# V1_1.net
KiCad netlist of a schematic drawn in EAGLE
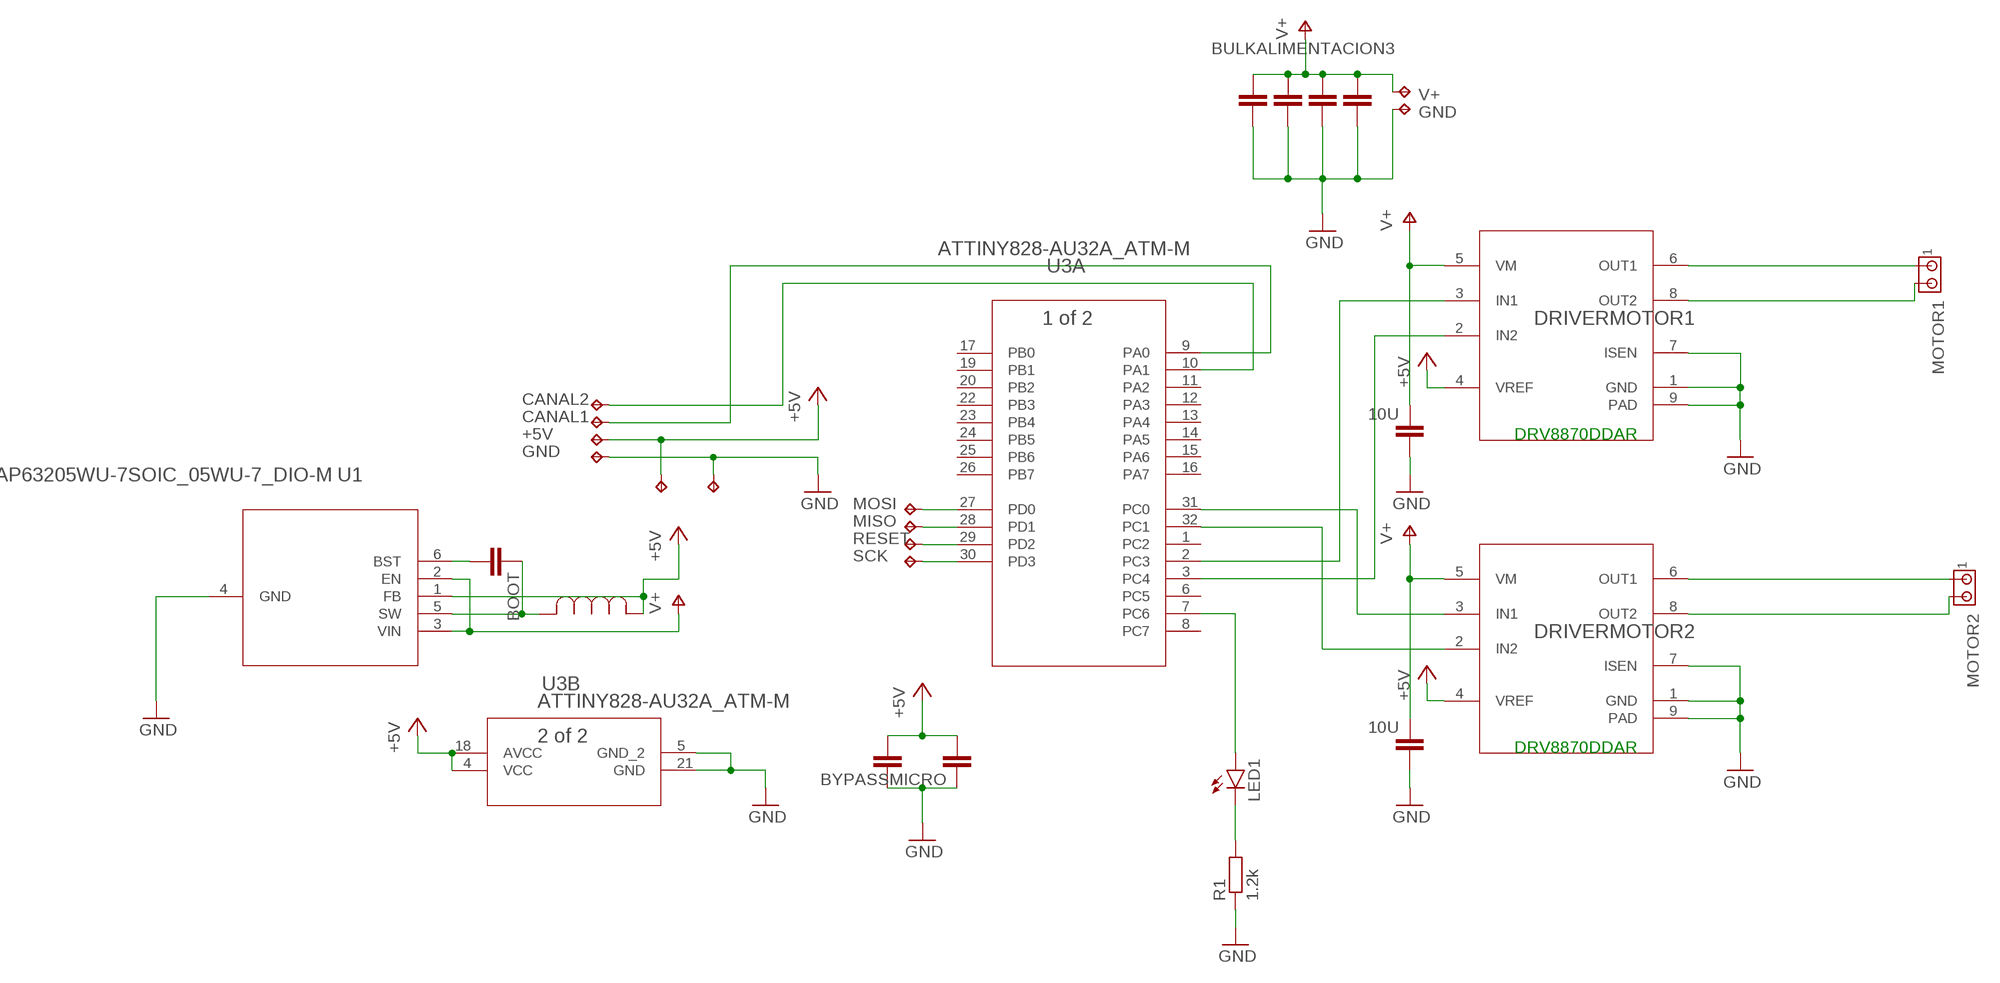
[diagram p0: schematic, sheet 1]

(export (version "E")
  (design (tool "Eeschema 10.0.6"))
  (components
    (comp (ref "BOOT")
      (value "C-EUC0402")
      (footprint "eagle-import:C0402")
      (libsource (lib "eagle-import") (part "C-EUC0402"))
    )
    (comp (ref "BULKALIMENTACION")
      (value "C-EUC1206")
      (footprint "eagle-import:C1206")
      (libsource (lib "eagle-import") (part "C-EUC1206"))
    )
    (comp (ref "BULKALIMENTACION1")
      (value "C-EUC1206")
      (footprint "eagle-import:C1206")
      (libsource (lib "eagle-import") (part "C-EUC1206"))
    )
    (comp (ref "BULKALIMENTACION2")
      (value "C-EUC1206")
      (footprint "eagle-import:C1206")
      (libsource (lib "eagle-import") (part "C-EUC1206"))
    )
    (comp (ref "BULKALIMENTACION3")
      (value "C-EUC1206")
      (footprint "eagle-import:C1206")
      (libsource (lib "eagle-import") (part "C-EUC1206"))
    )
    (comp (ref "BYPASS1")
      (value "10U")
      (footprint "eagle-import:C0603")
      (libsource (lib "eagle-import") (part "C-EUC0603"))
    )
    (comp (ref "BYPASSMICRO")
      (value "C-EUC0603")
      (footprint "eagle-import:C0603")
      (libsource (lib "eagle-import") (part "C-EUC0603"))
    )
    (comp (ref "BYPASSMICRO2")
      (value "C-EUC0603")
      (footprint "eagle-import:C0603")
      (libsource (lib "eagle-import") (part "C-EUC0603"))
    )
    (comp (ref "BYPASSMOTOR2")
      (value "10U")
      (footprint "eagle-import:C0603")
      (libsource (lib "eagle-import") (part "C-EUC0603"))
    )
    (comp (ref "DRIVERMOTOR1")
      (value "DRV8870")
      (footprint "eagle-import:DDA0008H_N")
      (libsource (lib "eagle-import") (part "DRV8870"))
    )
    (comp (ref "DRIVERMOTOR2")
      (value "DRV8870")
      (footprint "eagle-import:DDA0008H_N")
      (libsource (lib "eagle-import") (part "DRV8870"))
    )
    (comp (ref "GND")
      (value "TPTP20SQ")
      (footprint "eagle-import:TP20SQ")
      (libsource (lib "eagle-import") (part "TPTP20SQ"))
    )
    (comp (ref "LED1")
      (value "LEDCHIPLED_0603")
      (footprint "eagle-import:CHIPLED_0603")
      (libsource (lib "eagle-import") (part "LEDCHIPLED_0603"))
    )
    (comp (ref "MISO")
      (value "TPTP12R")
      (footprint "eagle-import:TP12R")
      (libsource (lib "eagle-import") (part "TPTP12R"))
    )
    (comp (ref "MOTOR1")
      (value "MTA02-100")
      (footprint "eagle-import:10X02MTA")
      (libsource (lib "eagle-import") (part "MTA02-100"))
    )
    (comp (ref "MOTOR2")
      (value "MTA02-100")
      (footprint "eagle-import:10X02MTA")
      (libsource (lib "eagle-import") (part "MTA02-100"))
    )
    (comp (ref "R1")
      (value "1.2k")
      (footprint "eagle-import:R0603")
      (libsource (lib "eagle-import") (part "R-EU_R0603"))
    )
    (comp (ref "TP1")
      (value "TPTP13SQ")
      (footprint "eagle-import:TP13SQ")
      (libsource (lib "eagle-import") (part "TPTP13SQ"))
    )
    (comp (ref "TP2")
      (value "TPTP13SQ")
      (footprint "eagle-import:TP13SQ")
      (libsource (lib "eagle-import") (part "TPTP13SQ"))
    )
    (comp (ref "TP3")
      (value "TPTP13SQ")
      (footprint "eagle-import:TP13SQ")
      (libsource (lib "eagle-import") (part "TPTP13SQ"))
    )
    (comp (ref "TP4")
      (value "TPTP13SQ")
      (footprint "eagle-import:TP13SQ")
      (libsource (lib "eagle-import") (part "TPTP13SQ"))
    )
    (comp (ref "TP5")
      (value "TPTP13SQ")
      (footprint "eagle-import:TP13SQ")
      (libsource (lib "eagle-import") (part "TPTP13SQ"))
    )
    (comp (ref "TP6")
      (value "TPTP12R")
      (footprint "eagle-import:TP12R")
      (libsource (lib "eagle-import") (part "TPTP12R"))
    )
    (comp (ref "TP7")
      (value "TPTP12R")
      (footprint "eagle-import:TP12R")
      (libsource (lib "eagle-import") (part "TPTP12R"))
    )
    (comp (ref "TP8")
      (value "TPTP12R")
      (footprint "eagle-import:TP12R")
      (libsource (lib "eagle-import") (part "TPTP12R"))
    )
    (comp (ref "TP9")
      (value "TPTP13SQ")
      (footprint "eagle-import:TP13SQ")
      (libsource (lib "eagle-import") (part "TPTP13SQ"))
    )
    (comp (ref "U$2")
      (value "INDUCTOR4.7")
      (footprint "eagle-import:IND_NRS5030T100MMGJ_TAY")
      (libsource (lib "eagle-import") (part "INDUCTOR4.7"))
    )
    (comp (ref "U1")
      (value "AP63205WU-7SOIC_05WU-7_DIO-M")
      (footprint "eagle-import:SOIC_05WU-7_DIO-M")
      (fields
        (field (name "MANUFACTURER_PART_NUMBER") "AP63205WU-7")
        (field (name "COPYRIGHT") "Copyright (C) 2018 Accelerated Designs. All rights reserved")
      )
      (libsource (lib "eagle-import") (part "AP63205WU-7SOIC_05WU-7_DIO-M"))
    )
    (comp (ref "U3")
      (value "ATTINY828-AU32A_ATM-M")
      (footprint "eagle-import:32A_ATM-M")
      (fields (field (name "MANUFACTURER_PART_NUMBER") "ATTINY828-AU"))
      (libsource (lib "eagle-import") (part "ATTINY828-AU32A_ATM-M"))
    )
    (comp (ref "V+")
      (value "TPTP20SQ")
      (footprint "eagle-import:TP20SQ")
      (libsource (lib "eagle-import") (part "TPTP20SQ"))
    )
  )
  (nets
    (net (code "1") (name "+5V") (class "Default")
      (node (ref "BYPASSMICRO") (pin "2") (pinfunction "2_2") (pintype "passive"))
      (node (ref "BYPASSMICRO2") (pin "2") (pinfunction "2_2") (pintype "passive"))
      (node (ref "DRIVERMOTOR1") (pin "4") (pinfunction "VREF_4") (pintype "input"))
      (node (ref "DRIVERMOTOR2") (pin "4") (pinfunction "VREF_4") (pintype "input"))
      (node (ref "TP3") (pin "TP") (pinfunction "TP_TP") (pintype "input"))
      (node (ref "TP9") (pin "TP") (pinfunction "TP_TP") (pintype "input"))
      (node (ref "U$2") (pin "1") (pinfunction "1_1") (pintype "passive"))
      (node (ref "U1") (pin "1") (pinfunction "FB_1") (pintype "passive"))
      (node (ref "U3") (pin "18") (pinfunction "AVCC_18") (pintype "power_in"))
      (node (ref "U3") (pin "4") (pinfunction "VCC_4") (pintype "power_in"))
    )
    (net (code "2") (name "/CANAL1") (class "Default")
      (node (ref "TP1") (pin "TP") (pinfunction "TP_TP") (pintype "input"))
      (node (ref "U3") (pin "9") (pinfunction "PA0_9") (pintype "bidirectional"))
    )
    (net (code "3") (name "/CANAL2") (class "Default")
      (node (ref "TP2") (pin "TP") (pinfunction "TP_TP") (pintype "input"))
      (node (ref "U3") (pin "10") (pinfunction "PA1_10") (pintype "bidirectional"))
    )
    (net (code "4") (name "/MISO") (class "Default")
      (node (ref "TP6") (pin "TP") (pinfunction "TP_TP") (pintype "input"))
      (node (ref "U3") (pin "28") (pinfunction "PD1_28") (pintype "bidirectional"))
    )
    (net (code "5") (name "/MOSI") (class "Default")
      (node (ref "MISO") (pin "TP") (pinfunction "TP_TP") (pintype "input"))
      (node (ref "U3") (pin "27") (pinfunction "PD0_27") (pintype "bidirectional"))
    )
    (net (code "6") (name "/RESET") (class "Default")
      (node (ref "TP7") (pin "TP") (pinfunction "TP_TP") (pintype "input"))
      (node (ref "U3") (pin "29") (pinfunction "PD2_29") (pintype "bidirectional"))
    )
    (net (code "7") (name "/SCK") (class "Default")
      (node (ref "TP8") (pin "TP") (pinfunction "TP_TP") (pintype "input"))
      (node (ref "U3") (pin "30") (pinfunction "PD3_30") (pintype "bidirectional"))
    )
    (net (code "8") (name "GND") (class "Default")
      (node (ref "BULKALIMENTACION") (pin "2") (pinfunction "2_2") (pintype "passive"))
      (node (ref "BULKALIMENTACION1") (pin "2") (pinfunction "2_2") (pintype "passive"))
      (node (ref "BULKALIMENTACION2") (pin "2") (pinfunction "2_2") (pintype "passive"))
      (node (ref "BULKALIMENTACION3") (pin "2") (pinfunction "2_2") (pintype "passive"))
      (node (ref "BYPASS1") (pin "1") (pinfunction "1_1") (pintype "passive"))
      (node (ref "BYPASSMICRO") (pin "1") (pinfunction "1_1") (pintype "passive"))
      (node (ref "BYPASSMICRO2") (pin "1") (pinfunction "1_1") (pintype "passive"))
      (node (ref "BYPASSMOTOR2") (pin "1") (pinfunction "1_1") (pintype "passive"))
      (node (ref "DRIVERMOTOR1") (pin "1") (pinfunction "GND_1") (pintype "power_in"))
      (node (ref "DRIVERMOTOR1") (pin "7") (pinfunction "ISEN_7") (pintype "input"))
      (node (ref "DRIVERMOTOR1") (pin "9") (pinfunction "PAD_9") (pintype "power_in"))
      (node (ref "DRIVERMOTOR2") (pin "1") (pinfunction "GND_1") (pintype "power_in"))
      (node (ref "DRIVERMOTOR2") (pin "7") (pinfunction "ISEN_7") (pintype "input"))
      (node (ref "DRIVERMOTOR2") (pin "9") (pinfunction "PAD_9") (pintype "power_in"))
      (node (ref "GND") (pin "TP") (pinfunction "TP_TP") (pintype "input"))
      (node (ref "R1") (pin "1") (pinfunction "1_1") (pintype "passive"))
      (node (ref "TP4") (pin "TP") (pinfunction "TP_TP") (pintype "input"))
      (node (ref "TP5") (pin "TP") (pinfunction "TP_TP") (pintype "input"))
      (node (ref "U1") (pin "4") (pinfunction "GND_4") (pintype "passive"))
      (node (ref "U3") (pin "21") (pinfunction "GND_21") (pintype "power_in"))
      (node (ref "U3") (pin "5") (pinfunction "GND_2_5") (pintype "power_in"))
    )
    (net (code "9") (name "Net-(DRIVERMOTOR1-IN1)") (class "Default")
      (node (ref "DRIVERMOTOR1") (pin "3") (pinfunction "IN1_3") (pintype "input"))
      (node (ref "U3") (pin "2") (pinfunction "PC3_2") (pintype "bidirectional"))
    )
    (net (code "10") (name "Net-(DRIVERMOTOR1-IN2)") (class "Default")
      (node (ref "DRIVERMOTOR1") (pin "2") (pinfunction "IN2_2") (pintype "input"))
      (node (ref "U3") (pin "3") (pinfunction "PC4_3") (pintype "bidirectional"))
    )
    (net (code "11") (name "Net-(DRIVERMOTOR1-OUT1)") (class "Default")
      (node (ref "DRIVERMOTOR1") (pin "6") (pinfunction "OUT1_6") (pintype "output"))
      (node (ref "MOTOR1") (pin "1") (pinfunction "1_1") (pintype "passive"))
    )
    (net (code "12") (name "Net-(DRIVERMOTOR1-OUT2)") (class "Default")
      (node (ref "DRIVERMOTOR1") (pin "8") (pinfunction "OUT2_8") (pintype "output"))
      (node (ref "MOTOR1") (pin "2") (pinfunction "2_2") (pintype "passive"))
    )
    (net (code "13") (name "Net-(DRIVERMOTOR2-IN1)") (class "Default")
      (node (ref "DRIVERMOTOR2") (pin "3") (pinfunction "IN1_3") (pintype "input"))
      (node (ref "U3") (pin "31") (pinfunction "PC0_31") (pintype "bidirectional"))
    )
    (net (code "14") (name "Net-(DRIVERMOTOR2-IN2)") (class "Default")
      (node (ref "DRIVERMOTOR2") (pin "2") (pinfunction "IN2_2") (pintype "input"))
      (node (ref "U3") (pin "32") (pinfunction "PC1_32") (pintype "bidirectional"))
    )
    (net (code "15") (name "Net-(DRIVERMOTOR2-OUT1)") (class "Default")
      (node (ref "DRIVERMOTOR2") (pin "6") (pinfunction "OUT1_6") (pintype "output"))
      (node (ref "MOTOR2") (pin "1") (pinfunction "1_1") (pintype "passive"))
    )
    (net (code "16") (name "Net-(DRIVERMOTOR2-OUT2)") (class "Default")
      (node (ref "DRIVERMOTOR2") (pin "8") (pinfunction "OUT2_8") (pintype "output"))
      (node (ref "MOTOR2") (pin "2") (pinfunction "2_2") (pintype "passive"))
    )
    (net (code "17") (name "Net-(LED1-PadC)") (class "Default")
      (node (ref "LED1") (pin "C") (pinfunction "C_C") (pintype "passive"))
      (node (ref "R1") (pin "2") (pinfunction "2_2") (pintype "passive"))
    )
    (net (code "18") (name "Net-(U1-BST)") (class "Default")
      (node (ref "BOOT") (pin "2") (pinfunction "2_2") (pintype "passive"))
      (node (ref "U1") (pin "6") (pinfunction "BST_6") (pintype "passive"))
    )
    (net (code "19") (name "Net-(U1-SW)") (class "Default")
      (node (ref "BOOT") (pin "1") (pinfunction "1_1") (pintype "passive"))
      (node (ref "U$2") (pin "2") (pinfunction "2_2") (pintype "passive"))
      (node (ref "U1") (pin "5") (pinfunction "SW_5") (pintype "passive"))
    )
    (net (code "20") (name "Net-(U3A-PC6)") (class "Default")
      (node (ref "LED1") (pin "A") (pinfunction "A_A") (pintype "passive"))
      (node (ref "U3") (pin "7") (pinfunction "PC6_7") (pintype "bidirectional"))
    )
    (net (code "21") (name "V+") (class "Default")
      (node (ref "BULKALIMENTACION") (pin "1") (pinfunction "1_1") (pintype "passive"))
      (node (ref "BULKALIMENTACION1") (pin "1") (pinfunction "1_1") (pintype "passive"))
      (node (ref "BULKALIMENTACION2") (pin "1") (pinfunction "1_1") (pintype "passive"))
      (node (ref "BULKALIMENTACION3") (pin "1") (pinfunction "1_1") (pintype "passive"))
      (node (ref "BYPASS1") (pin "2") (pinfunction "2_2") (pintype "passive"))
      (node (ref "BYPASSMOTOR2") (pin "2") (pinfunction "2_2") (pintype "passive"))
      (node (ref "DRIVERMOTOR1") (pin "5") (pinfunction "VM_5") (pintype "power_in"))
      (node (ref "DRIVERMOTOR2") (pin "5") (pinfunction "VM_5") (pintype "power_in"))
      (node (ref "U1") (pin "2") (pinfunction "EN_2") (pintype "passive"))
      (node (ref "U1") (pin "3") (pinfunction "VIN_3") (pintype "passive"))
      (node (ref "V+") (pin "TP") (pinfunction "TP_TP") (pintype "input"))
    )
    (net (code "22") (name "unconnected-(U3A-PA2-Pad11)") (class "Default")
      (node (ref "U3") (pin "11") (pinfunction "PA2_11") (pintype "bidirectional"))
    )
    (net (code "23") (name "unconnected-(U3A-PA3-Pad12)") (class "Default")
      (node (ref "U3") (pin "12") (pinfunction "PA3_12") (pintype "bidirectional"))
    )
    (net (code "24") (name "unconnected-(U3A-PA4-Pad13)") (class "Default")
      (node (ref "U3") (pin "13") (pinfunction "PA4_13") (pintype "bidirectional"))
    )
    (net (code "25") (name "unconnected-(U3A-PA5-Pad14)") (class "Default")
      (node (ref "U3") (pin "14") (pinfunction "PA5_14") (pintype "bidirectional"))
    )
    (net (code "26") (name "unconnected-(U3A-PA6-Pad15)") (class "Default")
      (node (ref "U3") (pin "15") (pinfunction "PA6_15") (pintype "bidirectional"))
    )
    (net (code "27") (name "unconnected-(U3A-PA7-Pad16)") (class "Default")
      (node (ref "U3") (pin "16") (pinfunction "PA7_16") (pintype "bidirectional"))
    )
    (net (code "28") (name "unconnected-(U3A-PB0-Pad17)") (class "Default")
      (node (ref "U3") (pin "17") (pinfunction "PB0_17") (pintype "bidirectional"))
    )
    (net (code "29") (name "unconnected-(U3A-PB1-Pad19)") (class "Default")
      (node (ref "U3") (pin "19") (pinfunction "PB1_19") (pintype "bidirectional"))
    )
    (net (code "30") (name "unconnected-(U3A-PB2-Pad20)") (class "Default")
      (node (ref "U3") (pin "20") (pinfunction "PB2_20") (pintype "bidirectional"))
    )
    (net (code "31") (name "unconnected-(U3A-PB3-Pad22)") (class "Default")
      (node (ref "U3") (pin "22") (pinfunction "PB3_22") (pintype "bidirectional"))
    )
    (net (code "32") (name "unconnected-(U3A-PB4-Pad23)") (class "Default")
      (node (ref "U3") (pin "23") (pinfunction "PB4_23") (pintype "bidirectional"))
    )
    (net (code "33") (name "unconnected-(U3A-PB5-Pad24)") (class "Default")
      (node (ref "U3") (pin "24") (pinfunction "PB5_24") (pintype "bidirectional"))
    )
    (net (code "34") (name "unconnected-(U3A-PB6-Pad25)") (class "Default")
      (node (ref "U3") (pin "25") (pinfunction "PB6_25") (pintype "bidirectional"))
    )
    (net (code "35") (name "unconnected-(U3A-PB7-Pad26)") (class "Default")
      (node (ref "U3") (pin "26") (pinfunction "PB7_26") (pintype "bidirectional"))
    )
    (net (code "36") (name "unconnected-(U3A-PC2-Pad1)") (class "Default")
      (node (ref "U3") (pin "1") (pinfunction "PC2_1") (pintype "bidirectional"))
    )
    (net (code "37") (name "unconnected-(U3A-PC5-Pad6)") (class "Default")
      (node (ref "U3") (pin "6") (pinfunction "PC5_6") (pintype "bidirectional"))
    )
    (net (code "38") (name "unconnected-(U3A-PC7-Pad8)") (class "Default")
      (node (ref "U3") (pin "8") (pinfunction "PC7_8") (pintype "bidirectional"))
    )
  )
)
